# NewTalphaTHM.net
KiCad netlist of a schematic drawn in EasyEDA Pro
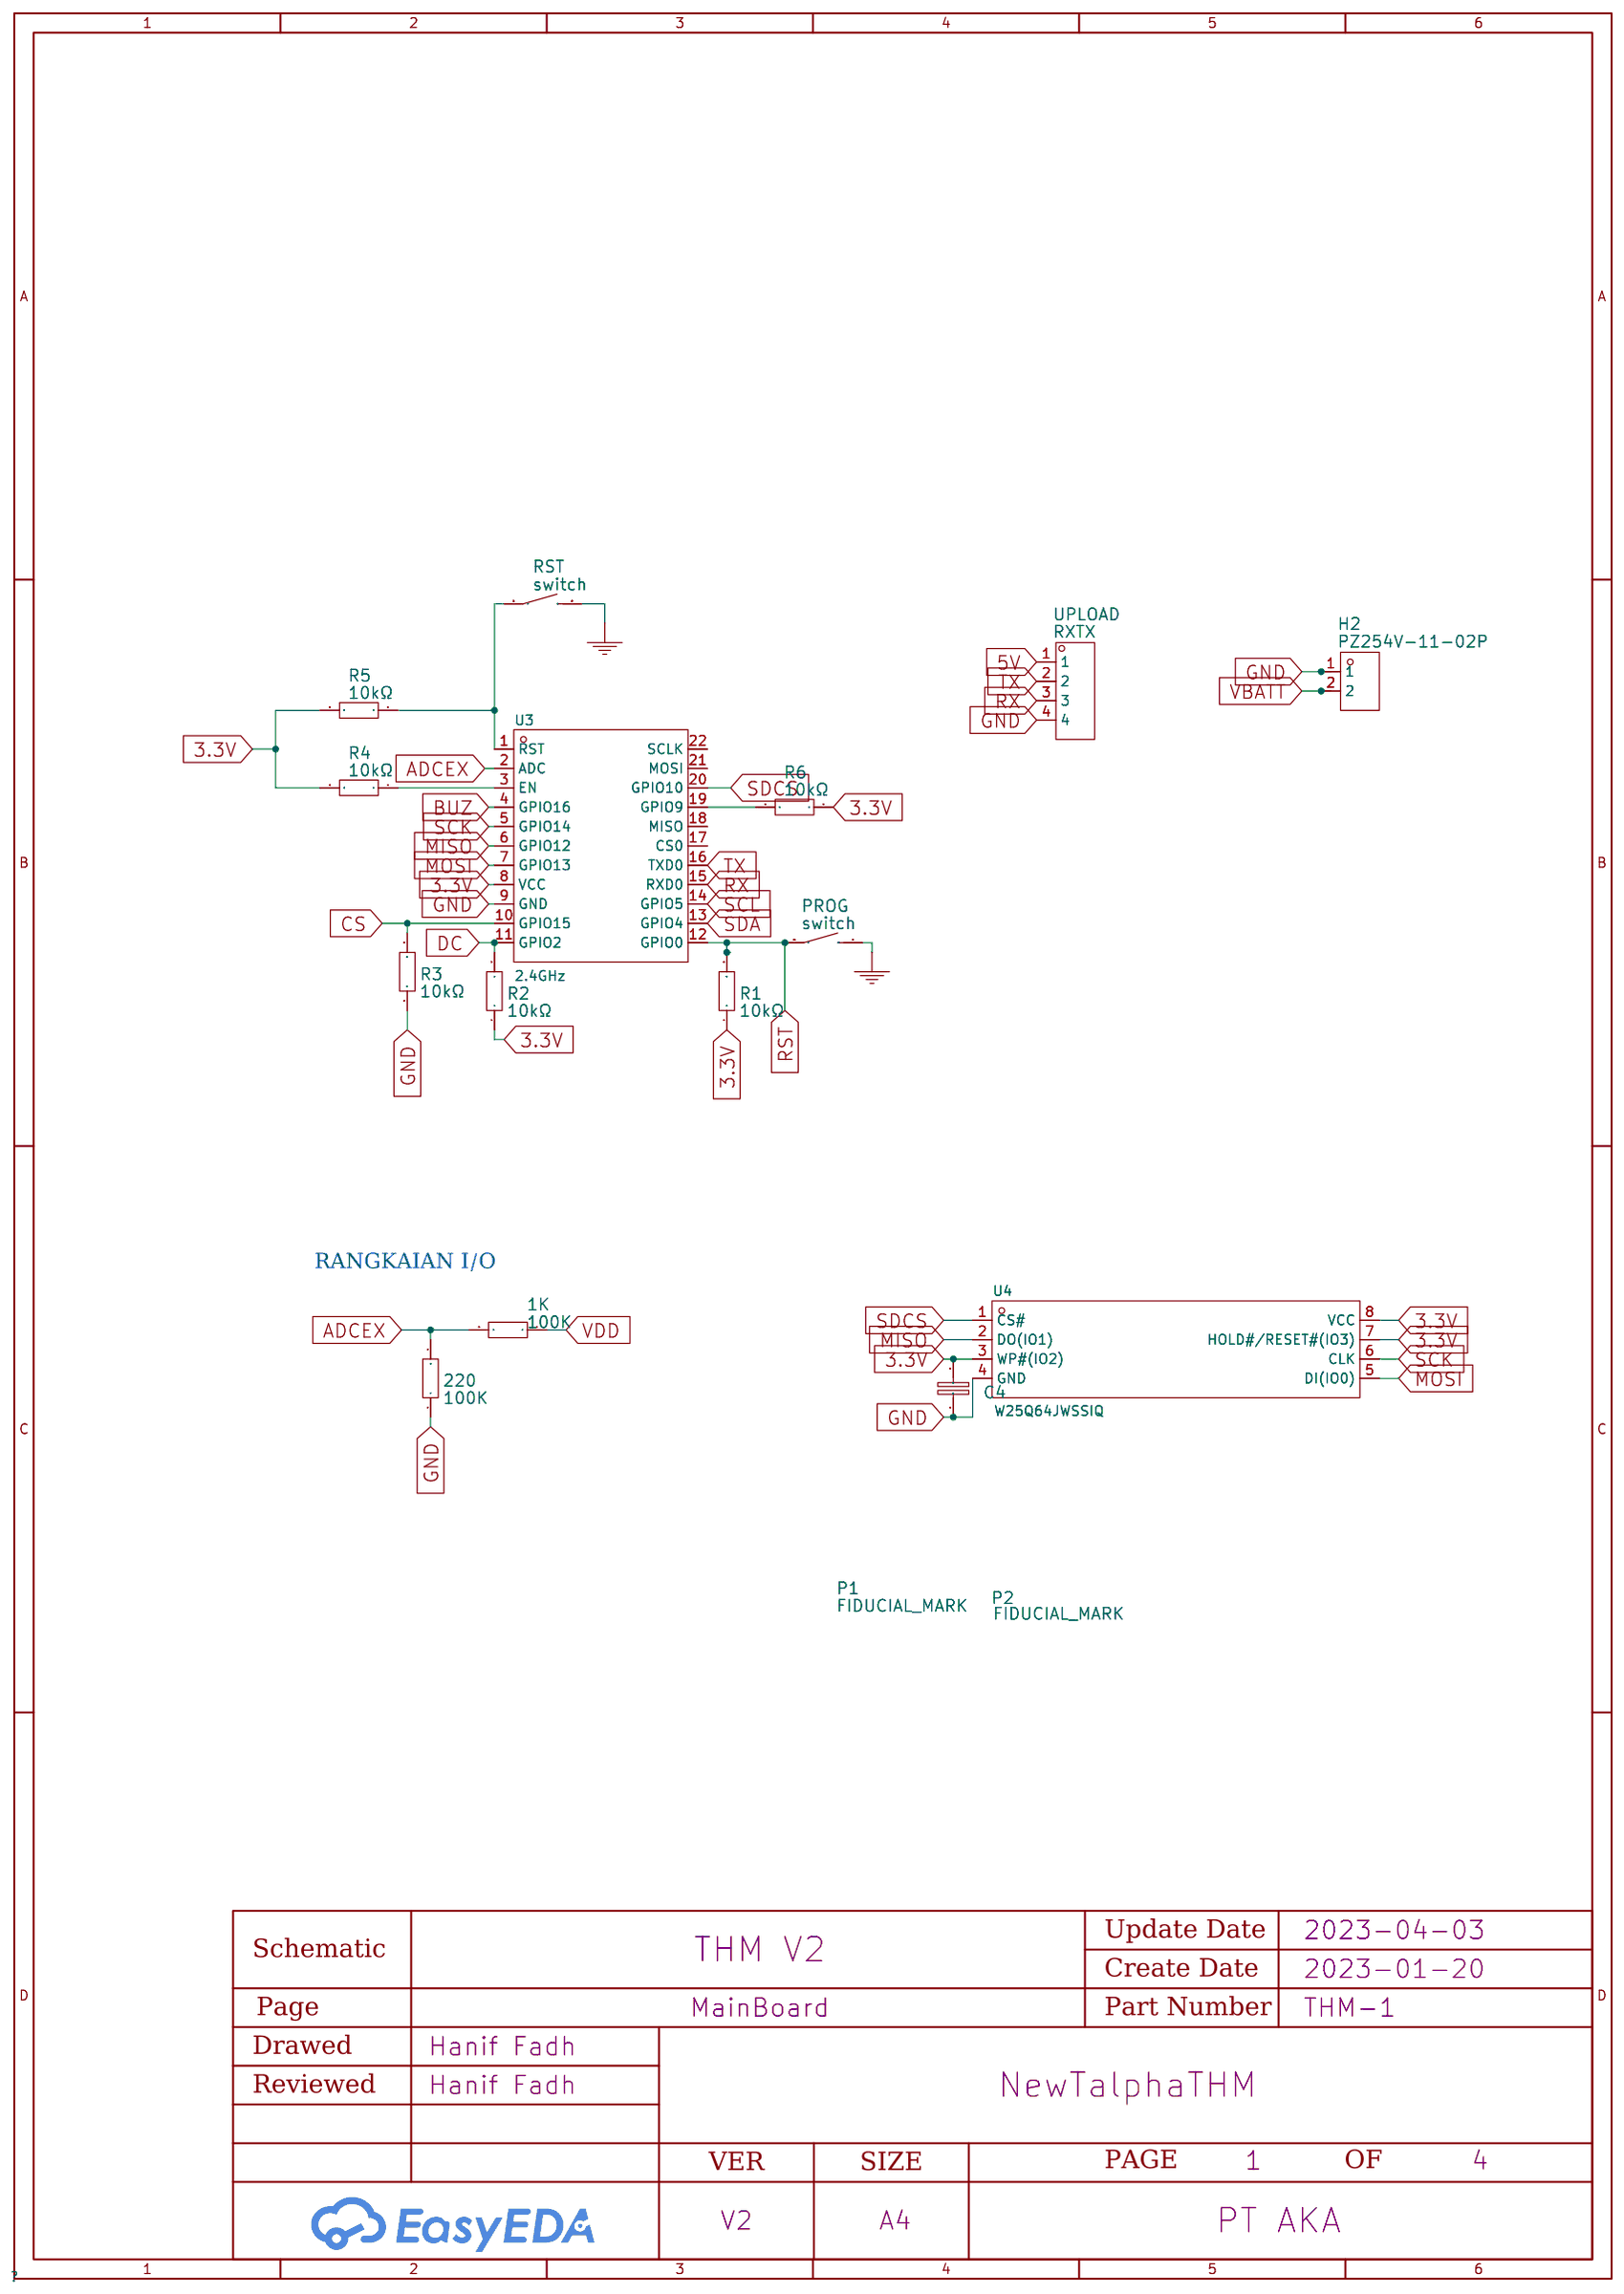
[diagram p0: MainBoard]
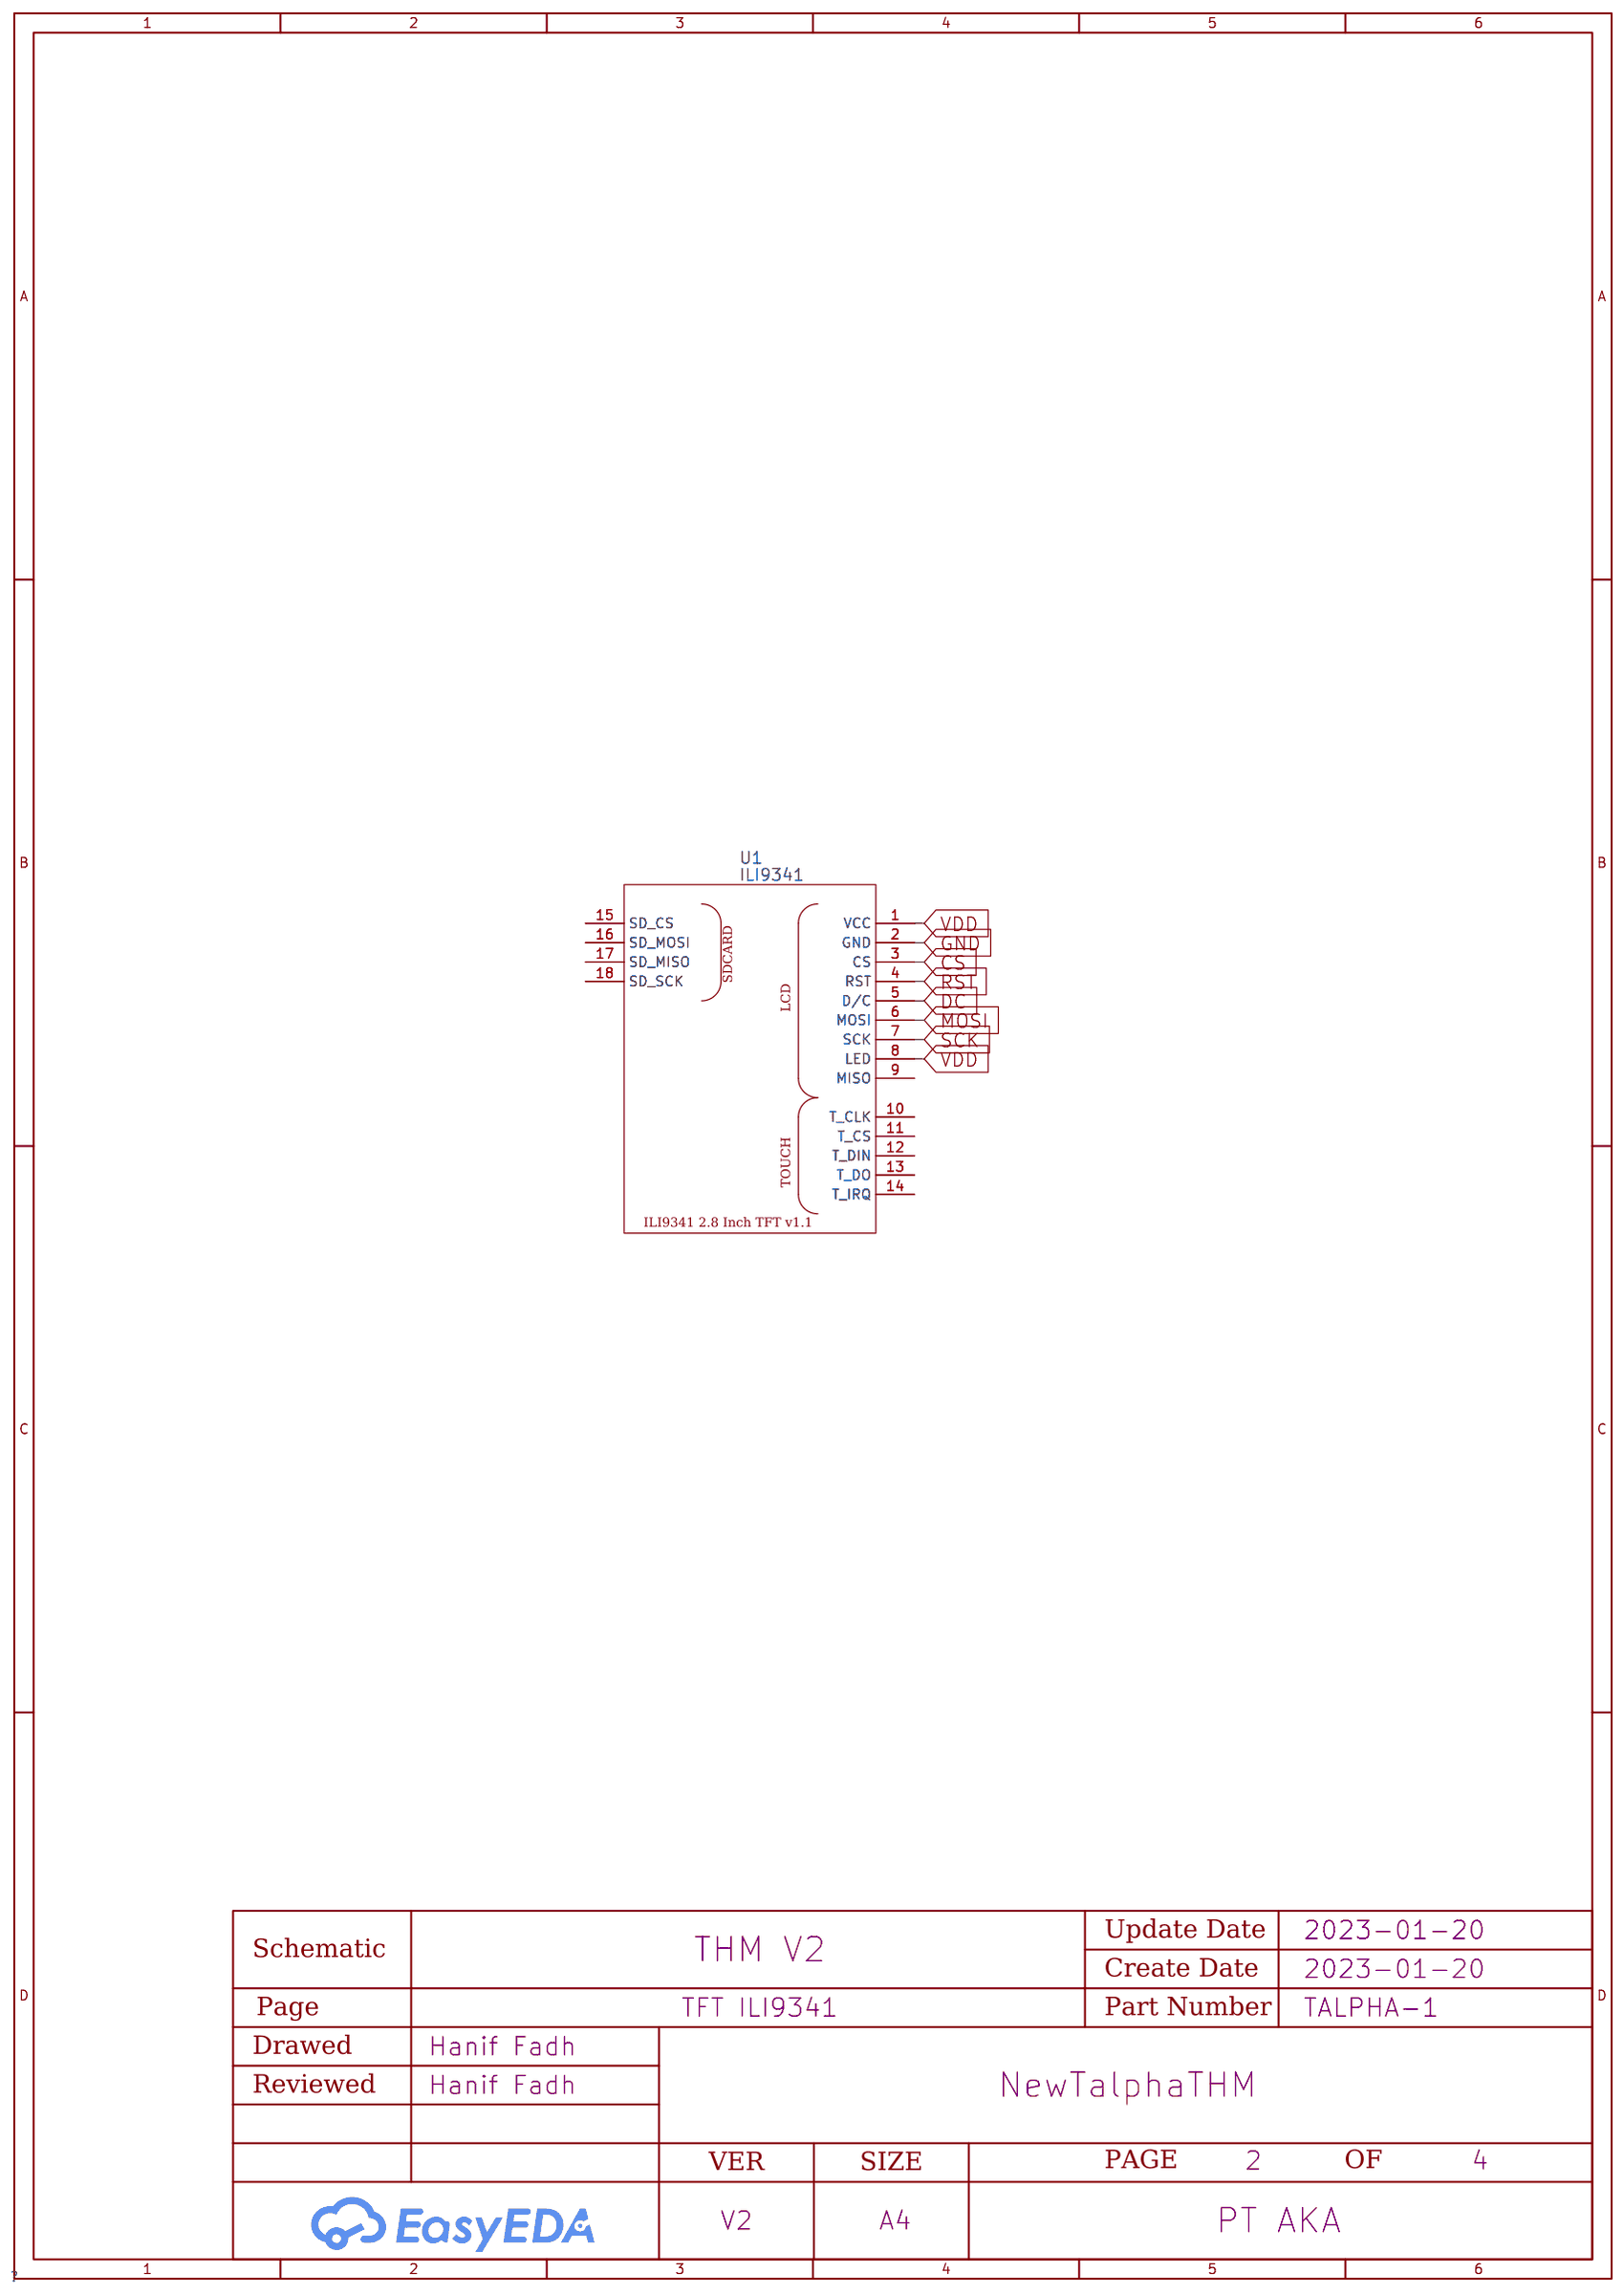
[diagram p1: TFT ILI9341]
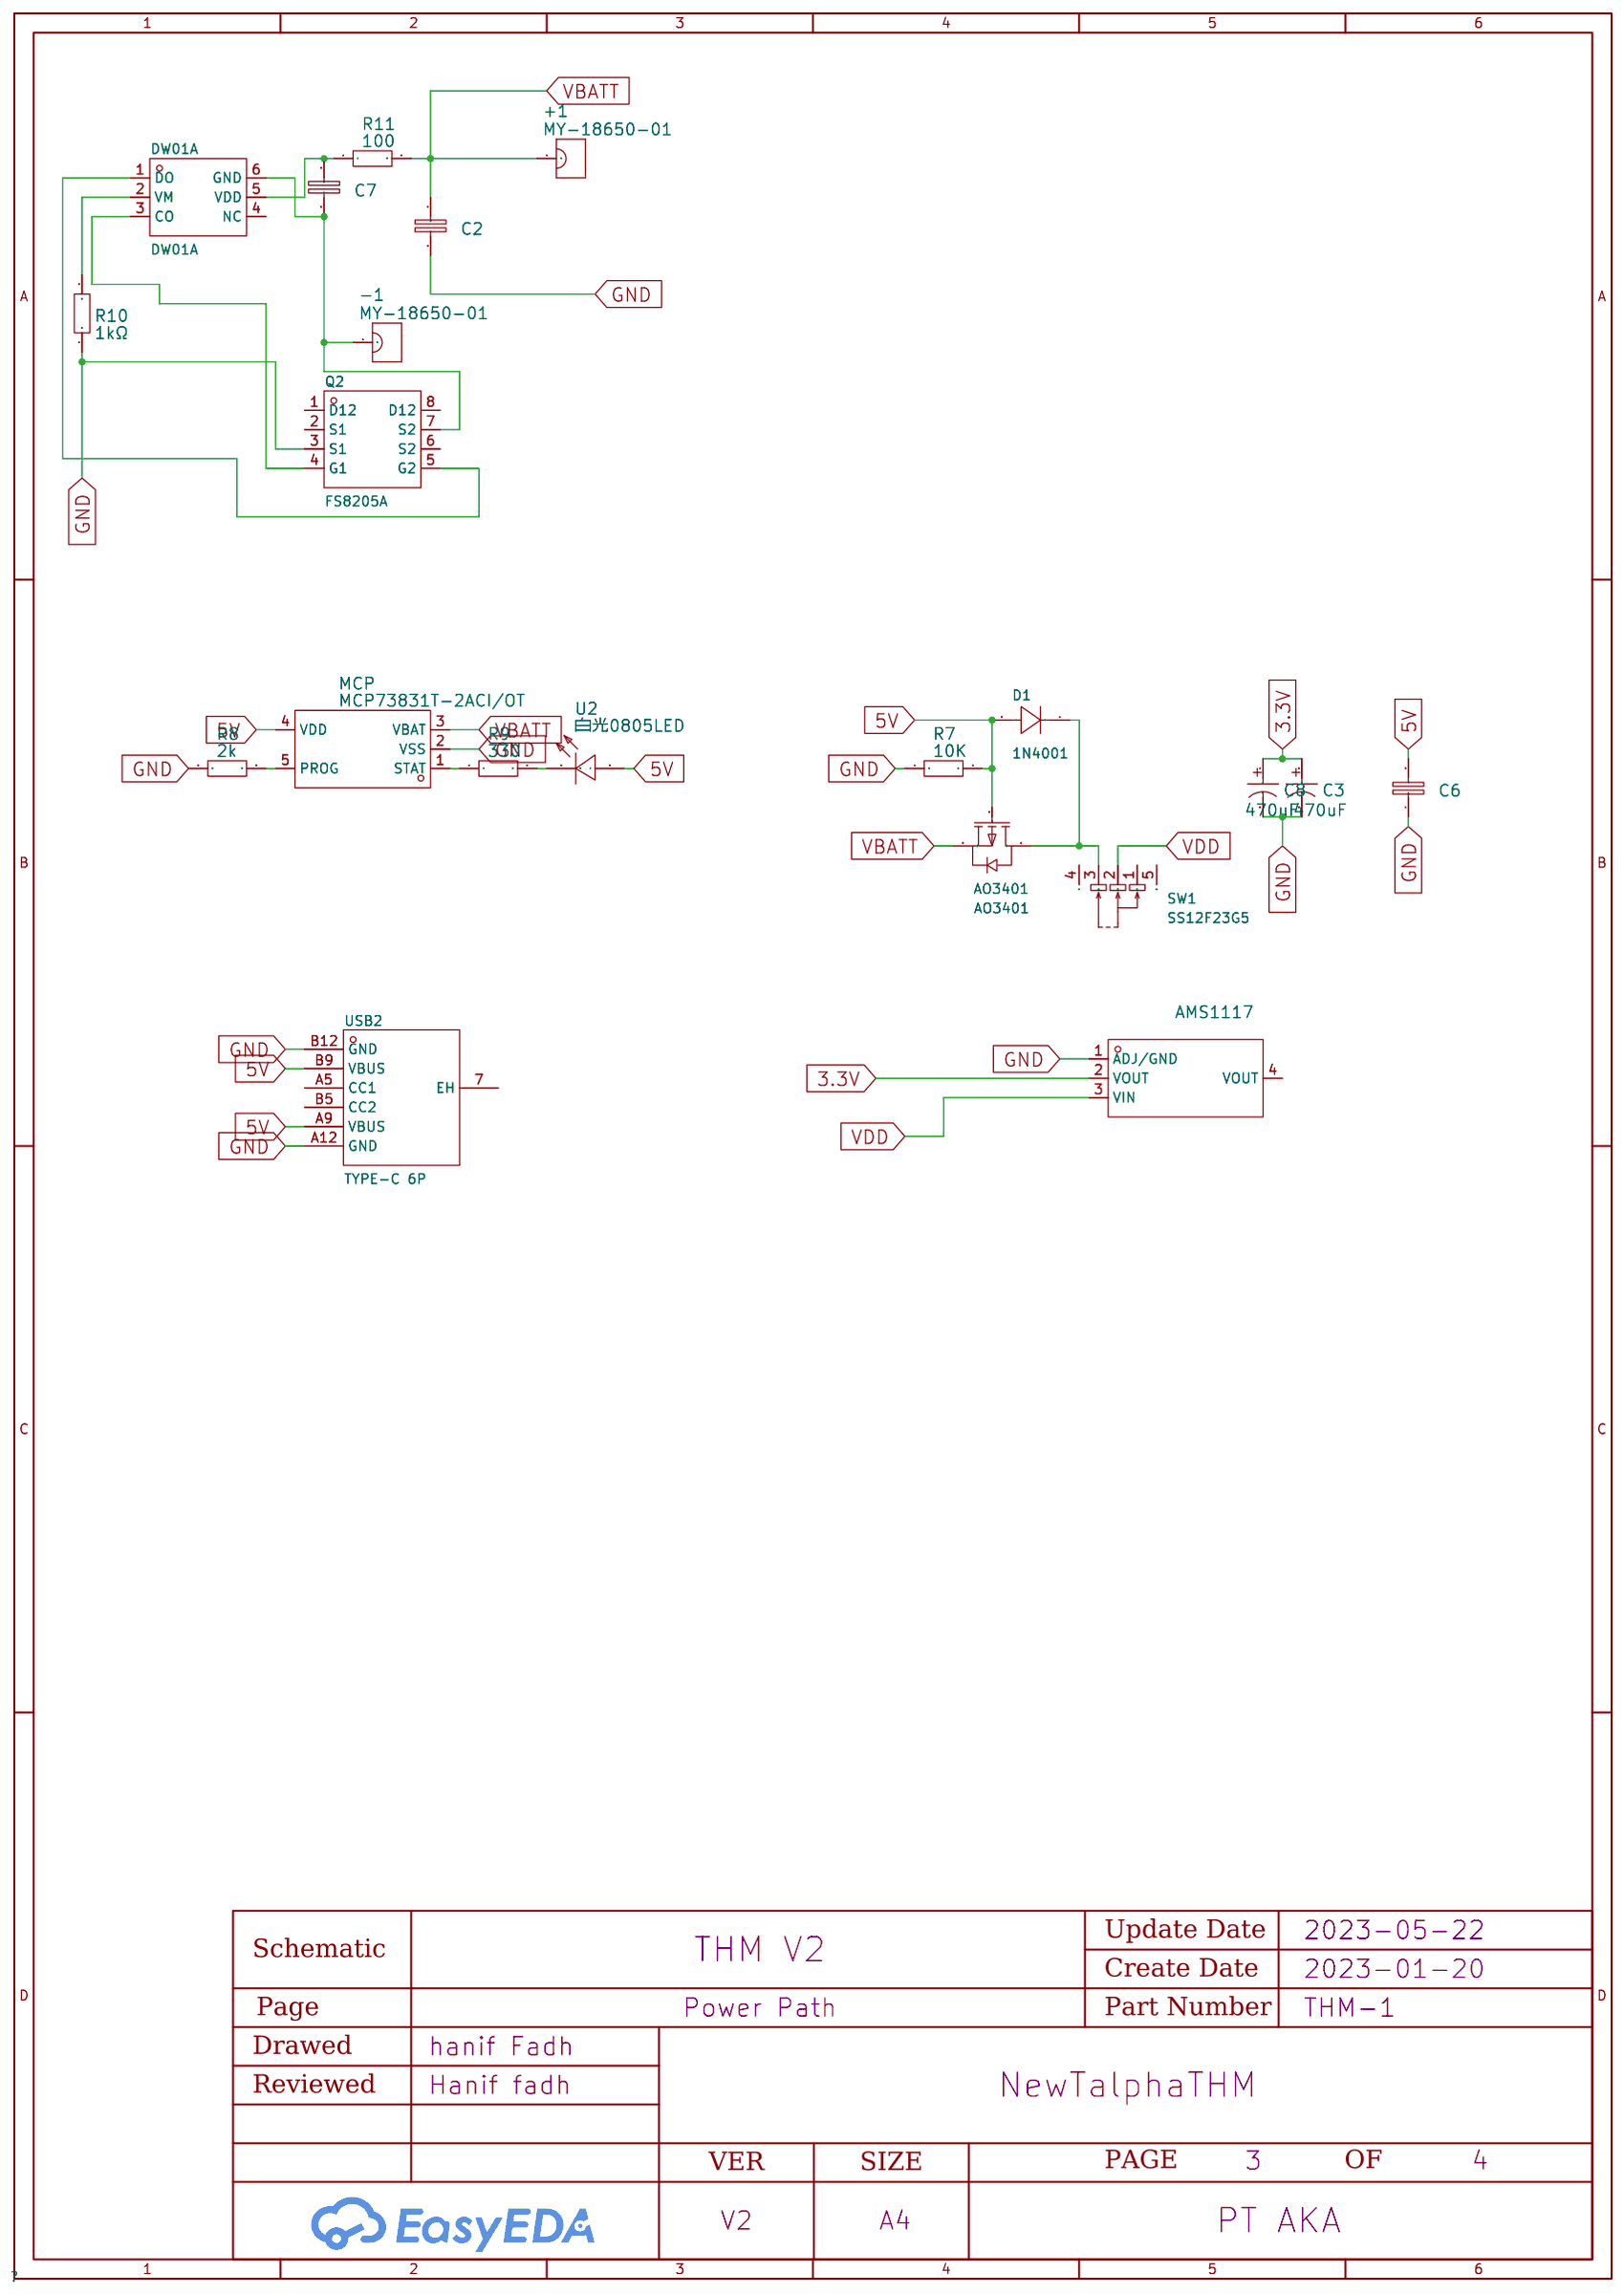
[diagram p2: Power Path]
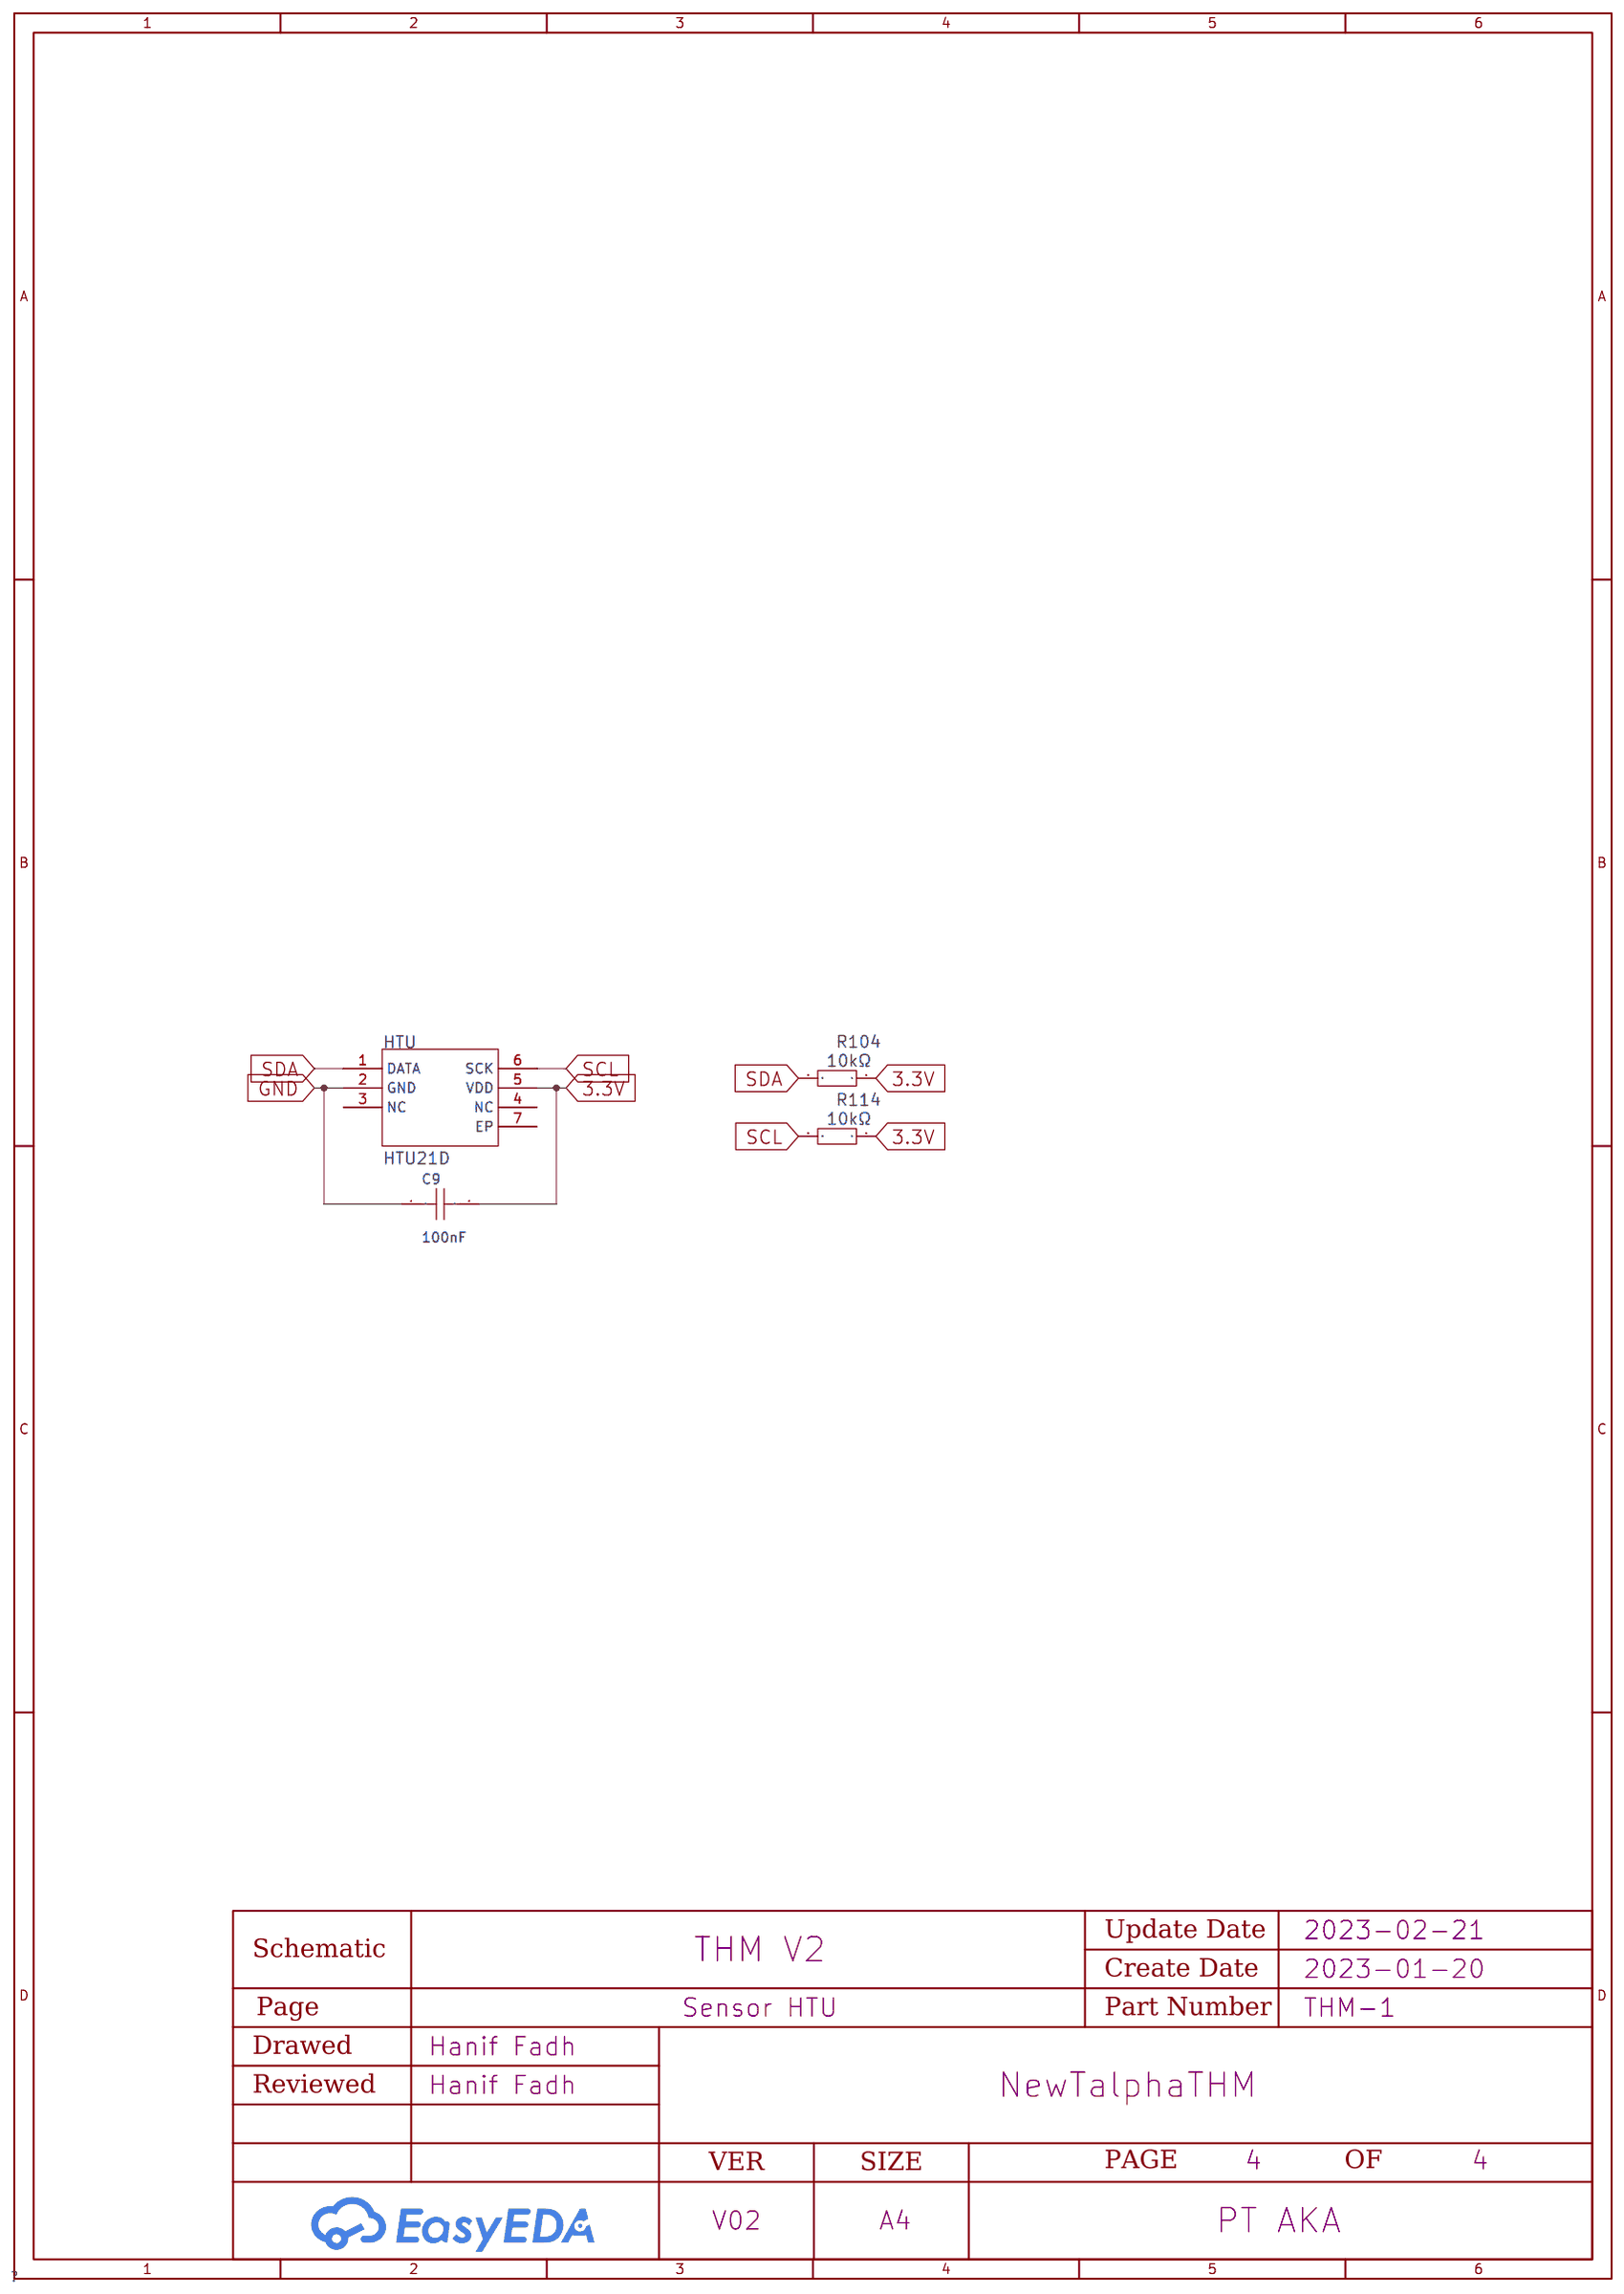
[diagram p3: Sensor HTU]

(export (version "E")
  (design (tool "Eeschema 10.0.6"))
  (components
    (comp (ref "1K")
      (value "100K")
      (footprint "easyedapro:R0805")
      (fields
        (field (name "Manufacturer Part") "AECR0805F100KK9")
        (field (name "Manufacturer") "ResistorToday")
      )
      (libsource (lib "easyedapro") (part "100K"))
    )
    (comp (ref "220")
      (value "100K")
      (footprint "easyedapro:R0805")
      (fields
        (field (name "Manufacturer Part") "AECR0805F100KK9")
        (field (name "Manufacturer") "ResistorToday")
      )
      (libsource (lib "easyedapro") (part "100K"))
    )
    (comp (ref "C4")
      (value "CSMD")
      (footprint "easyedapro:CAPACITOR-SMD")
      (libsource (lib "easyedapro") (part "CSMD"))
    )
    (comp (ref "H2")
      (value "PZ254V-11-02P")
      (footprint "easyedapro:HDR-TH_2P-P2.54-V-M")
      (fields (field (name "Manufacturer") "XFCN(兴飞)"))
      (libsource (lib "easyedapro") (part "PZ254V-11-02P"))
    )
    (comp (ref "P1")
      (value "FIDUCIAL_MARK")
      (footprint "easyedapro:FIDUCIAL_MARK")
      (libsource (lib "easyedapro") (part "FIDUCIAL_MARK"))
    )
    (comp (ref "P2")
      (value "FIDUCIAL_MARK")
      (footprint "easyedapro:FIDUCIAL_MARK")
      (libsource (lib "easyedapro") (part "FIDUCIAL_MARK"))
    )
    (comp (ref "PROG")
      (value "switch")
      (footprint "easyedapro:TACTILE-SWITCH-1101NE")
      (libsource (lib "easyedapro") (part "switch"))
    )
    (comp (ref "R1")
      (value "10kΩ")
      (footprint "easyedapro:R0805")
      (fields
        (field (name "Manufacturer Part") "0805W8F1002T5E")
        (field (name "Manufacturer") "UNI-ROYAL(厚声)")
      )
      (libsource (lib "easyedapro") (part "10kΩ"))
    )
    (comp (ref "R2")
      (value "10kΩ")
      (footprint "easyedapro:R0805")
      (fields
        (field (name "Manufacturer Part") "0805W8F1002T5E")
        (field (name "Manufacturer") "UNI-ROYAL(厚声)")
      )
      (libsource (lib "easyedapro") (part "10kΩ"))
    )
    (comp (ref "R3")
      (value "10kΩ")
      (footprint "easyedapro:R0805")
      (fields
        (field (name "Manufacturer Part") "0805W8F1002T5E")
        (field (name "Manufacturer") "UNI-ROYAL(厚声)")
      )
      (libsource (lib "easyedapro") (part "10kΩ"))
    )
    (comp (ref "R4")
      (value "10kΩ")
      (footprint "easyedapro:R0805")
      (fields
        (field (name "Manufacturer Part") "0805W8F1002T5E")
        (field (name "Manufacturer") "UNI-ROYAL(厚声)")
      )
      (libsource (lib "easyedapro") (part "10kΩ"))
    )
    (comp (ref "R5")
      (value "10kΩ")
      (footprint "easyedapro:R0805")
      (fields
        (field (name "Manufacturer Part") "0805W8F1002T5E")
        (field (name "Manufacturer") "UNI-ROYAL(厚声)")
      )
      (libsource (lib "easyedapro") (part "10kΩ"))
    )
    (comp (ref "R6")
      (value "10kΩ")
      (footprint "easyedapro:R0805")
      (fields
        (field (name "Manufacturer Part") "0805W8F1002T5E")
        (field (name "Manufacturer") "UNI-ROYAL(厚声)")
      )
      (libsource (lib "easyedapro") (part "10kΩ"))
    )
    (comp (ref "RST")
      (value "switch")
      (footprint "easyedapro:TACTILE-SWITCH-1101NE")
      (libsource (lib "easyedapro") (part "switch"))
    )
    (comp (ref "U3")
      (value "2.4GHz")
      (footprint "easyedapro:WIFIM-SMD_ESP-12F-ESP8266MOD")
      (fields
        (field (name "Manufacturer Part") "ESP-12F(ESP8266MOD)")
        (field (name "Manufacturer") "Ai-Thinker(安信可)")
      )
      (libsource (lib "easyedapro") (part "ESP-12F(ESP8266MOD)"))
    )
    (comp (ref "U4")
      (value "W25Q64JWSSIQ")
      (footprint "easyedapro:SOIC-8_L5.3-W5.3-P1.27-LS8.0-BL")
      (fields (field (name "Manufacturer") "WINBOND(华邦)"))
      (libsource (lib "easyedapro") (part "W25Q64JWSSIQ_C2985658"))
    )
    (comp (ref "UPLOAD")
      (value "RXTX")
      (footprint "easyedapro:HDR-TH_4P-P2.54-V-M")
      (fields
        (field (name "Manufacturer Part") "Headers  Pins 1*4P")
        (field (name "Manufacturer") "ReliaPro")
      )
      (libsource (lib "easyedapro") (part "RXTX"))
    )
    (comp (ref "U1")
      (value "ILI9341")
      (footprint "easyedapro:ILI9341-2.8")
      (libsource (lib "easyedapro") (part "ILI9341"))
    )
    (comp (ref "+1")
      (value "MY-18650-01")
      (footprint "easyedapro:BAT-TH_MY-18650-01")
      (fields (field (name "Manufacturer") "MYOUNG(美阳)"))
      (libsource (lib "easyedapro") (part "MY-18650-01"))
    )
    (comp (ref "-1")
      (value "MY-18650-01")
      (footprint "easyedapro:BAT-TH_MY-18650-01")
      (fields (field (name "Manufacturer") "MYOUNG(美阳)"))
      (libsource (lib "easyedapro") (part "MY-18650-01"))
    )
    (comp (ref "AMS1117")
      (value "AMS1117-3.3_C426566")
      (footprint "easyedapro:SOT-223_L6.5-W3.5-P2.30-LS7.0-BR")
      (fields
        (field (name "Manufacturer Part") "AMS1117-3.3")
        (field (name "Manufacturer") "SLKORMICRO Elec.")
      )
      (libsource (lib "easyedapro") (part "AMS1117-3.3_C426566"))
    )
    (comp (ref "AO3401")
      (value "AO3401")
      (footprint "easyedapro:SOT-23-3_L2.9-W1.4-P1.90-LS2.6-BR")
      (fields (field (name "Manufacturer") "TWGMC(台湾迪嘉)"))
      (libsource (lib "easyedapro") (part "AO3401_C727156"))
    )
    (comp (ref "C2")
      (value "CSMD")
      (footprint "easyedapro:CAPACITOR-SMD")
      (libsource (lib "easyedapro") (part "CSMD"))
    )
    (comp (ref "C3")
      (value "470uF")
      (footprint "easyedapro:CAP-SMD_L7.3-W4.3")
      (fields (field (name "Manufacturer Part") "TAJE477K006RNJ") (field (name "Manufacturer") "AVX"))
      (libsource (lib "easyedapro") (part "470uF"))
    )
    (comp (ref "C6")
      (value "4.7uf")
      (footprint "easyedapro:CAPACITOR-SMD")
      (libsource (lib "easyedapro") (part "4.7uf"))
    )
    (comp (ref "C7")
      (value "CSMD")
      (footprint "easyedapro:CAPACITOR-SMD")
      (libsource (lib "easyedapro") (part "CSMD"))
    )
    (comp (ref "C8")
      (value "470uF")
      (footprint "easyedapro:CAP-SMD_L7.3-W4.3")
      (fields (field (name "Manufacturer Part") "TAJE477K006RNJ") (field (name "Manufacturer") "AVX"))
      (libsource (lib "easyedapro") (part "470uF"))
    )
    (comp (ref "D1")
      (value "1N4001")
      (footprint "easyedapro:SMA_L4.3-W2.5-LS5.0-RD")
      (fields (field (name "Manufacturer") "TWGMC(台湾迪嘉)"))
      (libsource (lib "easyedapro") (part "1N4001_C727079"))
    )
    (comp (ref "DW01A")
      (value "DW01A")
      (footprint "easyedapro:SOT-23-6_L2.9-W1.6-P0.95-LS2.8-BL")
      (fields (field (name "Manufacturer") "TF(拓锋)"))
      (libsource (lib "easyedapro") (part "DW01A_C436931"))
    )
    (comp (ref "MCP")
      (value "MCP73831T-2ACI/OT")
      (footprint "easyedapro:SOT-23-5_L3.0-W1.7-P0.95-LS2.8-BR")
      (fields (field (name "Manufacturer") "Microchip Tech"))
      (libsource (lib "easyedapro") (part "MCP73831T-2ACI/OT"))
    )
    (comp (ref "Q2")
      (value "FS8205A")
      (footprint "easyedapro:TSSOP-8_L4.4-W3.0-P0.65-LS6.4-BL-2")
      (fields (field (name "Manufacturer") "FORTUNE(富晶)"))
      (libsource (lib "easyedapro") (part "FS8205A"))
    )
    (comp (ref "R7")
      (value "10K")
      (footprint "easyedapro:0805")
      (fields
        (field (name "Manufacturer Part") "PTFR0805B110RN9")
        (field (name "Manufacturer") "ResistorToday")
      )
      (libsource (lib "easyedapro") (part "330"))
    )
    (comp (ref "R8")
      (value "2k")
      (footprint "easyedapro:0805")
      (fields
        (field (name "Manufacturer Part") "PTFR0805B110RN9")
        (field (name "Manufacturer") "ResistorToday")
      )
      (libsource (lib "easyedapro") (part "330"))
    )
    (comp (ref "R9")
      (value "330")
      (footprint "easyedapro:0805")
      (fields
        (field (name "Manufacturer Part") "PTFR0805B110RN9")
        (field (name "Manufacturer") "ResistorToday")
      )
      (libsource (lib "easyedapro") (part "330"))
    )
    (comp (ref "R10")
      (value "1kΩ")
      (footprint "easyedapro:R0805")
      (fields
        (field (name "Manufacturer Part") "0805W8F1002T5E")
        (field (name "Manufacturer") "UNI-ROYAL(厚声)")
      )
      (libsource (lib "easyedapro") (part "10kΩ"))
    )
    (comp (ref "R11")
      (value "100")
      (footprint "easyedapro:0805")
      (fields
        (field (name "Manufacturer Part") "PTFR0805B110RN9")
        (field (name "Manufacturer") "ResistorToday")
      )
      (libsource (lib "easyedapro") (part "330"))
    )
    (comp (ref "SW1")
      (value "SS12F23G5")
      (footprint "easyedapro:SW-TH_SHOU-HAN_SS12F23G5")
      (fields (field (name "Manufacturer") "SHOU HAN(首韩)"))
      (libsource (lib "easyedapro") (part "SS12F23G5"))
    )
    (comp (ref "U2")
      (value "白光0805LED")
      (footprint "easyedapro:LED0805-RD_WHITE")
      (libsource (lib "easyedapro") (part "白光0805LED"))
    )
    (comp (ref "USB2")
      (value "TYPE-C 6P")
      (footprint "easyedapro:TYPE-C-SMD_TYPE-C-6P")
      (fields (field (name "Manufacturer") "SHOU HAN(首韩)"))
      (libsource (lib "easyedapro") (part "TYPE-C 6P"))
    )
    (comp (ref "C9")
      (value "100nF")
      (footprint "easyedapro:C0805")
      (fields (field (name "Manufacturer Part") "C0805X104K101TB") (field (name "Manufacturer") "IHHEC(禾伸堂)"))
      (libsource (lib "easyedapro") (part "C0805X104K101TB"))
    )
    (comp (ref "HTU")
      (value "HTU21D")
      (footprint "easyedapro:DFN-6_L3.0-W3.0-P1.00-BL-EP")
      (fields (field (name "Manufacturer") "TE Connectivity(美国泰科)"))
      (libsource (lib "easyedapro") (part "HTU21D"))
    )
    (comp (ref "R104")
      (value "10kΩ")
      (footprint "easyedapro:R0805")
      (fields
        (field (name "Manufacturer Part") "0805W8F1002T5E")
        (field (name "Manufacturer") "UNI-ROYAL(厚声)")
      )
      (libsource (lib "easyedapro") (part "10kΩ"))
    )
    (comp (ref "R114")
      (value "10kΩ")
      (footprint "easyedapro:R0805")
      (fields
        (field (name "Manufacturer Part") "0805W8F1002T5E")
        (field (name "Manufacturer") "UNI-ROYAL(厚声)")
      )
      (libsource (lib "easyedapro") (part "10kΩ"))
    )
  )
  (nets
    (net (code "1") (name "3.3V") (class "Default")
      (node (ref "AMS1117") (pin "2") (pinfunction "VOUT_2") (pintype "input"))
      (node (ref "C3") (pin "1") (pinfunction "1_1") (pintype "input"))
      (node (ref "C4") (pin "2") (pinfunction "2_2") (pintype "bidirectional"))
      (node (ref "C8") (pin "1") (pinfunction "1_1") (pintype "input"))
      (node (ref "C9") (pin "2") (pinfunction "2_2") (pintype "input"))
      (node (ref "HTU") (pin "5") (pinfunction "VDD_5") (pintype "input"))
      (node (ref "R1") (pin "1") (pinfunction "1_1") (pintype "input"))
      (node (ref "R104") (pin "1") (pinfunction "1_1") (pintype "input"))
      (node (ref "R114") (pin "1") (pinfunction "1_1") (pintype "input"))
      (node (ref "R2") (pin "1") (pinfunction "1_1") (pintype "input"))
      (node (ref "R4") (pin "2") (pinfunction "2_2") (pintype "input"))
      (node (ref "R5") (pin "2") (pinfunction "2_2") (pintype "input"))
      (node (ref "R6") (pin "1") (pinfunction "1_1") (pintype "input"))
      (node (ref "U3") (pin "8") (pinfunction "VCC_8") (pintype "input"))
      (node (ref "U4") (pin "3") (pinfunction "WP#(IO2)_3") (pintype "input"))
      (node (ref "U4") (pin "7") (pinfunction "HOLD#/RESET#(IO3)_7") (pintype "input"))
      (node (ref "U4") (pin "8") (pinfunction "VCC_8") (pintype "input"))
    )
    (net (code "2") (name "5V") (class "Default")
      (node (ref "AO3401") (pin "1") (pinfunction "G_1") (pintype "input"))
      (node (ref "C6") (pin "2") (pinfunction "2_2") (pintype "bidirectional"))
      (node (ref "D1") (pin "2") (pinfunction "A_2") (pintype "input"))
      (node (ref "MCP") (pin "4") (pinfunction "VDD_4") (pintype "input"))
      (node (ref "R7") (pin "2") (pinfunction "2_2") (pintype "input"))
      (node (ref "U2") (pin "2") (pinfunction "A_2") (pintype "input"))
      (node (ref "UPLOAD") (pin "1") (pinfunction "1_1") (pintype "input"))
      (node (ref "USB2") (pin "A9") (pinfunction "VBUS_A9") (pintype "input"))
      (node (ref "USB2") (pin "B9") (pinfunction "VBUS_B9") (pintype "input"))
    )
    (net (code "3") (name "ADCEX") (class "Default")
      (node (ref "1K") (pin "2") (pinfunction "2_2") (pintype "input"))
      (node (ref "220") (pin "2") (pinfunction "2_2") (pintype "input"))
      (node (ref "U3") (pin "2") (pinfunction "ADC_2") (pintype "input"))
    )
    (net (code "4") (name "BUZ") (class "Default")
      (node (ref "U3") (pin "4") (pinfunction "GPIO16_4") (pintype "input"))
    )
    (net (code "5") (name "CS") (class "Default")
      (node (ref "R3") (pin "2") (pinfunction "2_2") (pintype "input"))
      (node (ref "U1") (pin "3") (pinfunction "CS_3") (pintype "input"))
      (node (ref "U3") (pin "10") (pinfunction "GPIO15_10") (pintype "input"))
    )
    (net (code "6") (name "DC") (class "Default")
      (node (ref "R2") (pin "2") (pinfunction "2_2") (pintype "input"))
      (node (ref "U1") (pin "5") (pinfunction "D/C_5") (pintype "input"))
      (node (ref "U3") (pin "11") (pinfunction "GPIO2_11") (pintype "input"))
    )
    (net (code "7") (name "GND") (class "Default")
      (node (ref "220") (pin "1") (pinfunction "1_1") (pintype "input"))
      (node (ref "AMS1117") (pin "1") (pinfunction "ADJ/GND_1") (pintype "input"))
      (node (ref "C2") (pin "2") (pinfunction "2_2") (pintype "bidirectional"))
      (node (ref "C3") (pin "2") (pinfunction "2_2") (pintype "input"))
      (node (ref "C4") (pin "1") (pinfunction "1_1") (pintype "bidirectional"))
      (node (ref "C6") (pin "1") (pinfunction "1_1") (pintype "bidirectional"))
      (node (ref "C8") (pin "2") (pinfunction "2_2") (pintype "input"))
      (node (ref "C9") (pin "1") (pinfunction "1_1") (pintype "input"))
      (node (ref "H2") (pin "1") (pinfunction "1_1") (pintype "input"))
      (node (ref "HTU") (pin "2") (pinfunction "GND_2") (pintype "input"))
      (node (ref "MCP") (pin "2") (pinfunction "VSS_2") (pintype "input"))
      (node (ref "PROG") (pin "P$2") (pinfunction "2_P$2") (pintype "bidirectional"))
      (node (ref "Q2") (pin "3") (pinfunction "S1_3") (pintype "input"))
      (node (ref "R10") (pin "1") (pinfunction "1_1") (pintype "input"))
      (node (ref "R3") (pin "1") (pinfunction "1_1") (pintype "input"))
      (node (ref "R7") (pin "1") (pinfunction "1_1") (pintype "input"))
      (node (ref "R8") (pin "1") (pinfunction "1_1") (pintype "input"))
      (node (ref "RST") (pin "P$2") (pinfunction "2_P$2") (pintype "bidirectional"))
      (node (ref "U1") (pin "2") (pinfunction "GND_2") (pintype "input"))
      (node (ref "U3") (pin "9") (pinfunction "GND_9") (pintype "input"))
      (node (ref "U4") (pin "4") (pinfunction "GND_4") (pintype "input"))
      (node (ref "UPLOAD") (pin "4") (pinfunction "4_4") (pintype "input"))
      (node (ref "USB2") (pin "A12") (pinfunction "GND_A12") (pintype "input"))
      (node (ref "USB2") (pin "B12") (pinfunction "GND_B12") (pintype "input"))
    )
    (net (code "8") (name "MISO") (class "Default")
      (node (ref "U3") (pin "6") (pinfunction "GPIO12_6") (pintype "input"))
      (node (ref "U4") (pin "2") (pinfunction "DO(IO1)_2") (pintype "input"))
    )
    (net (code "9") (name "MOSI") (class "Default")
      (node (ref "U1") (pin "6") (pinfunction "MOSI_6") (pintype "input"))
      (node (ref "U3") (pin "7") (pinfunction "GPIO13_7") (pintype "input"))
      (node (ref "U4") (pin "5") (pinfunction "DI(IO0)_5") (pintype "input"))
    )
    (net (code "10") (name "Net-(AO3401-D)") (class "Default")
      (node (ref "AO3401") (pin "3") (pinfunction "D_3") (pintype "input"))
      (node (ref "D1") (pin "1") (pinfunction "K_1") (pintype "input"))
      (node (ref "SW1") (pin "3") (pinfunction "3_3") (pintype "input"))
    )
    (net (code "11") (name "Net-(DW01A-CO)") (class "Default")
      (node (ref "DW01A") (pin "3") (pinfunction "CO_3") (pintype "input"))
      (node (ref "Q2") (pin "4") (pinfunction "G1_4") (pintype "input"))
    )
    (net (code "12") (name "Net-(DW01A-DO)") (class "Default")
      (node (ref "DW01A") (pin "1") (pinfunction "DO_1") (pintype "input"))
      (node (ref "Q2") (pin "5") (pinfunction "G2_5") (pintype "input"))
    )
    (net (code "13") (name "Net-(DW01A-GND)") (class "Default")
      (node (ref "-1") (pin "1") (pinfunction "1_1") (pintype "input"))
      (node (ref "C7") (pin "2") (pinfunction "2_2") (pintype "bidirectional"))
      (node (ref "DW01A") (pin "6") (pinfunction "GND_6") (pintype "input"))
      (node (ref "Q2") (pin "7") (pinfunction "S2_7") (pintype "input"))
    )
    (net (code "14") (name "Net-(DW01A-VDD)") (class "Default")
      (node (ref "C7") (pin "1") (pinfunction "1_1") (pintype "bidirectional"))
      (node (ref "DW01A") (pin "5") (pinfunction "VDD_5") (pintype "input"))
      (node (ref "R11") (pin "1") (pinfunction "1_1") (pintype "input"))
    )
    (net (code "15") (name "Net-(DW01A-VM)") (class "Default")
      (node (ref "DW01A") (pin "2") (pinfunction "VM_2") (pintype "input"))
      (node (ref "R10") (pin "2") (pinfunction "2_2") (pintype "input"))
    )
    (net (code "16") (name "Net-(MCP-PROG)") (class "Default")
      (node (ref "MCP") (pin "5") (pinfunction "PROG_5") (pintype "input"))
      (node (ref "R8") (pin "2") (pinfunction "2_2") (pintype "input"))
    )
    (net (code "17") (name "Net-(MCP-STAT)") (class "Default")
      (node (ref "MCP") (pin "1") (pinfunction "STAT_1") (pintype "input"))
      (node (ref "R9") (pin "1") (pinfunction "1_1") (pintype "input"))
    )
    (net (code "18") (name "Net-(RST-1)") (class "Default")
      (node (ref "R5") (pin "1") (pinfunction "1_1") (pintype "input"))
      (node (ref "RST") (pin "P$1") (pinfunction "1_P$1") (pintype "bidirectional"))
      (node (ref "U3") (pin "1") (pinfunction "RST_1") (pintype "input"))
    )
    (net (code "19") (name "Net-(U2-C)") (class "Default")
      (node (ref "R9") (pin "2") (pinfunction "2_2") (pintype "input"))
      (node (ref "U2") (pin "1") (pinfunction "C_1") (pintype "input"))
    )
    (net (code "20") (name "Net-(U3-EN)") (class "Default")
      (node (ref "R4") (pin "1") (pinfunction "1_1") (pintype "input"))
      (node (ref "U3") (pin "3") (pinfunction "EN_3") (pintype "input"))
    )
    (net (code "21") (name "Net-(U3-GPIO9)") (class "Default")
      (node (ref "R6") (pin "2") (pinfunction "2_2") (pintype "input"))
      (node (ref "U3") (pin "19") (pinfunction "GPIO9_19") (pintype "input"))
    )
    (net (code "22") (name "RST") (class "Default")
      (node (ref "PROG") (pin "P$1") (pinfunction "1_P$1") (pintype "bidirectional"))
      (node (ref "R1") (pin "2") (pinfunction "2_2") (pintype "input"))
      (node (ref "U1") (pin "4") (pinfunction "RST_4") (pintype "input"))
      (node (ref "U3") (pin "12") (pinfunction "GPIO0_12") (pintype "input"))
    )
    (net (code "23") (name "RX") (class "Default")
      (node (ref "U3") (pin "15") (pinfunction "RXD0_15") (pintype "input"))
      (node (ref "UPLOAD") (pin "3") (pinfunction "3_3") (pintype "input"))
    )
    (net (code "24") (name "SCK") (class "Default")
      (node (ref "U1") (pin "7") (pinfunction "SCK_7") (pintype "input"))
      (node (ref "U3") (pin "5") (pinfunction "GPIO14_5") (pintype "input"))
      (node (ref "U4") (pin "6") (pinfunction "CLK_6") (pintype "input"))
    )
    (net (code "25") (name "SCL") (class "Default")
      (node (ref "HTU") (pin "6") (pinfunction "SCK_6") (pintype "input"))
      (node (ref "R114") (pin "2") (pinfunction "2_2") (pintype "input"))
      (node (ref "U3") (pin "14") (pinfunction "GPIO5_14") (pintype "input"))
    )
    (net (code "26") (name "SDA") (class "Default")
      (node (ref "HTU") (pin "1") (pinfunction "DATA_1") (pintype "input"))
      (node (ref "R104") (pin "2") (pinfunction "2_2") (pintype "input"))
      (node (ref "U3") (pin "13") (pinfunction "GPIO4_13") (pintype "input"))
    )
    (net (code "27") (name "SDCS") (class "Default")
      (node (ref "U3") (pin "20") (pinfunction "GPIO10_20") (pintype "input"))
      (node (ref "U4") (pin "1") (pinfunction "CS#_1") (pintype "input"))
    )
    (net (code "28") (name "TX") (class "Default")
      (node (ref "U3") (pin "16") (pinfunction "TXD0_16") (pintype "input"))
      (node (ref "UPLOAD") (pin "2") (pinfunction "2_2") (pintype "input"))
    )
    (net (code "29") (name "VBATT") (class "Default")
      (node (ref "+1") (pin "1") (pinfunction "1_1") (pintype "input"))
      (node (ref "AO3401") (pin "2") (pinfunction "S_2") (pintype "input"))
      (node (ref "C2") (pin "1") (pinfunction "1_1") (pintype "bidirectional"))
      (node (ref "H2") (pin "2") (pinfunction "2_2") (pintype "input"))
      (node (ref "MCP") (pin "3") (pinfunction "VBAT_3") (pintype "input"))
      (node (ref "R11") (pin "2") (pinfunction "2_2") (pintype "input"))
    )
    (net (code "30") (name "VDD") (class "Default")
      (node (ref "1K") (pin "1") (pinfunction "1_1") (pintype "input"))
      (node (ref "AMS1117") (pin "3") (pinfunction "VIN_3") (pintype "input"))
      (node (ref "SW1") (pin "2") (pinfunction "2_2") (pintype "input"))
      (node (ref "U1") (pin "1") (pinfunction "VCC_1") (pintype "input"))
      (node (ref "U1") (pin "8") (pinfunction "LED_8") (pintype "input"))
    )
    (net (code "31") (name "unconnected-(AMS1117-VOUT-Pad4)") (class "Default")
      (node (ref "AMS1117") (pin "4") (pinfunction "VOUT_4") (pintype "input"))
    )
    (net (code "32") (name "unconnected-(DW01A-NC-Pad4)") (class "Default")
      (node (ref "DW01A") (pin "4") (pinfunction "NC_4") (pintype "input"))
    )
    (net (code "33") (name "unconnected-(HTU-EP-Pad7)") (class "Default")
      (node (ref "HTU") (pin "7") (pinfunction "EP_7") (pintype "input"))
    )
    (net (code "34") (name "unconnected-(HTU-NC-Pad3)") (class "Default")
      (node (ref "HTU") (pin "3") (pinfunction "NC_3") (pintype "input"))
    )
    (net (code "35") (name "unconnected-(HTU-NC-Pad4)") (class "Default")
      (node (ref "HTU") (pin "4") (pinfunction "NC_4") (pintype "input"))
    )
    (net (code "36") (name "unconnected-(Q2-D12-Pad1)") (class "Default")
      (node (ref "Q2") (pin "1") (pinfunction "D12_1") (pintype "input"))
    )
    (net (code "37") (name "unconnected-(Q2-D12-Pad8)") (class "Default")
      (node (ref "Q2") (pin "8") (pinfunction "D12_8") (pintype "input"))
    )
    (net (code "38") (name "unconnected-(Q2-S1-Pad2)") (class "Default")
      (node (ref "Q2") (pin "2") (pinfunction "S1_2") (pintype "input"))
    )
    (net (code "39") (name "unconnected-(Q2-S2-Pad6)") (class "Default")
      (node (ref "Q2") (pin "6") (pinfunction "S2_6") (pintype "input"))
    )
    (net (code "40") (name "unconnected-(SW1-Pad1)") (class "Default")
      (node (ref "SW1") (pin "1") (pinfunction "1_1") (pintype "input"))
    )
    (net (code "41") (name "unconnected-(SW1-Pad4)") (class "Default")
      (node (ref "SW1") (pin "4") (pinfunction "4_4") (pintype "input"))
    )
    (net (code "42") (name "unconnected-(SW1-Pad5)") (class "Default")
      (node (ref "SW1") (pin "5") (pinfunction "5_5") (pintype "input"))
    )
    (net (code "43") (name "unconnected-(U1-MISO-Pad9)") (class "Default")
      (node (ref "U1") (pin "9") (pinfunction "MISO_9") (pintype "input"))
    )
    (net (code "44") (name "unconnected-(U1-SD_CS-Pad15)") (class "Default")
      (node (ref "U1") (pin "15") (pinfunction "SD_CS_15") (pintype "input"))
    )
    (net (code "45") (name "unconnected-(U1-SD_MISO-Pad17)") (class "Default")
      (node (ref "U1") (pin "17") (pinfunction "SD_MISO_17") (pintype "input"))
    )
    (net (code "46") (name "unconnected-(U1-SD_MOSI-Pad16)") (class "Default")
      (node (ref "U1") (pin "16") (pinfunction "SD_MOSI_16") (pintype "input"))
    )
    (net (code "47") (name "unconnected-(U1-SD_SCK-Pad18)") (class "Default")
      (node (ref "U1") (pin "18") (pinfunction "SD_SCK_18") (pintype "input"))
    )
    (net (code "48") (name "unconnected-(U1-T_CLK-Pad10)") (class "Default")
      (node (ref "U1") (pin "10") (pinfunction "T_CLK_10") (pintype "input"))
    )
    (net (code "49") (name "unconnected-(U1-T_CS-Pad11)") (class "Default")
      (node (ref "U1") (pin "11") (pinfunction "T_CS_11") (pintype "input"))
    )
    (net (code "50") (name "unconnected-(U1-T_DIN-Pad12)") (class "Default")
      (node (ref "U1") (pin "12") (pinfunction "T_DIN_12") (pintype "input"))
    )
    (net (code "51") (name "unconnected-(U1-T_DO-Pad13)") (class "Default")
      (node (ref "U1") (pin "13") (pinfunction "T_DO_13") (pintype "input"))
    )
    (net (code "52") (name "unconnected-(U1-T_IRQ-Pad14)") (class "Default")
      (node (ref "U1") (pin "14") (pinfunction "T_IRQ_14") (pintype "input"))
    )
    (net (code "53") (name "unconnected-(U3-CS0-Pad17)") (class "Default")
      (node (ref "U3") (pin "17") (pinfunction "CS0_17") (pintype "input"))
    )
    (net (code "54") (name "unconnected-(U3-MISO-Pad18)") (class "Default")
      (node (ref "U3") (pin "18") (pinfunction "MISO_18") (pintype "input"))
    )
    (net (code "55") (name "unconnected-(U3-MOSI-Pad21)") (class "Default")
      (node (ref "U3") (pin "21") (pinfunction "MOSI_21") (pintype "input"))
    )
    (net (code "56") (name "unconnected-(U3-SCLK-Pad22)") (class "Default")
      (node (ref "U3") (pin "22") (pinfunction "SCLK_22") (pintype "input"))
    )
    (net (code "57") (name "unconnected-(USB2-CC1-PadA5)") (class "Default")
      (node (ref "USB2") (pin "A5") (pinfunction "CC1_A5") (pintype "input"))
    )
    (net (code "58") (name "unconnected-(USB2-CC2-PadB5)") (class "Default")
      (node (ref "USB2") (pin "B5") (pinfunction "CC2_B5") (pintype "input"))
    )
    (net (code "59") (name "unconnected-(USB2-EH-Pad7)") (class "Default")
      (node (ref "USB2") (pin "7") (pinfunction "EH_7") (pintype "input"))
    )
  )
)
